# MSI001_MSI2500.net
KiCad netlist of a schematic drawn in Altium Designer
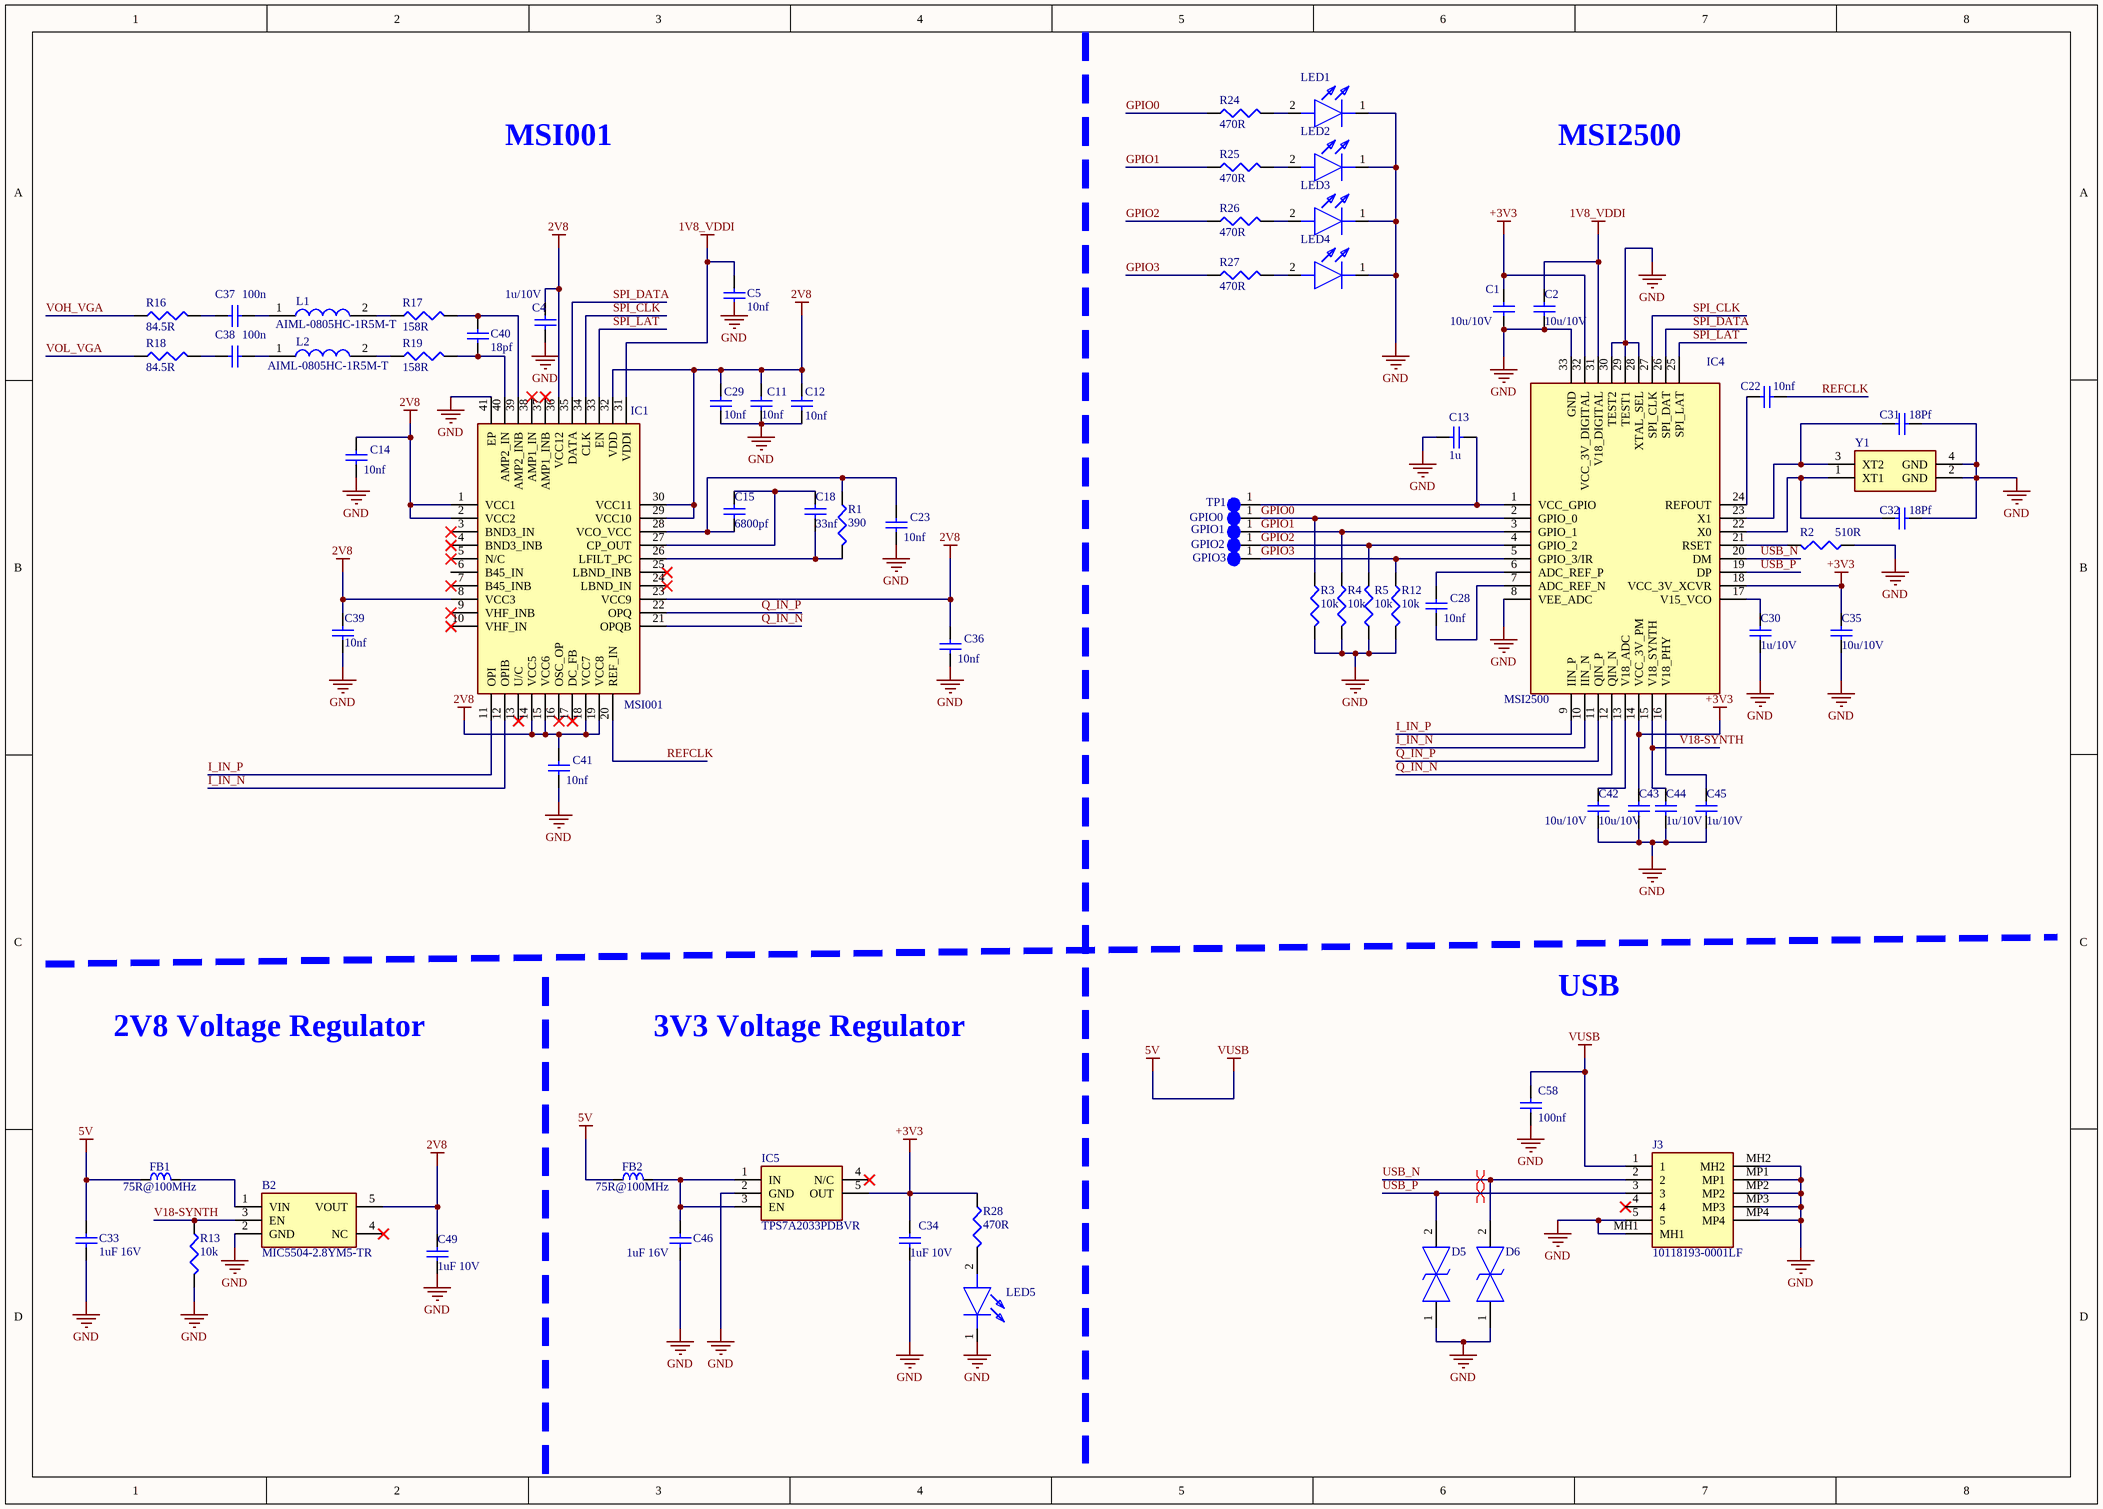
[diagram p0: MSI001 & MSI2500 .SchDoc]

(export (version "E")
  (design (tool "Eeschema 10.0.6"))
  (components
    (comp (ref "B2")
      (value "MIC5504-2.8YM5-TR")
      (footprint "SOT95P280X145-5N")
      (description "MICROCHIP - MIC5504-2.8YM5-TR - LDO VOLT REG, 0.3A, 2.8V, SOT-23-5")
      (fields (field (name "MOUSER PART NUMBER") "998-MIC5504-2.8YM5TR"))
      (libsource (lib "MIC5504-2.8YM5-TR") (part "MIC5504-2.8YM5-TR"))
    )
    (comp (ref "C1")
      (value "10u/10V")
      (footprint "0402_C")
      (description "Capacitor  0603 inch")
      (fields (field (name "Comment") "cap0603") (field (name "PUBLISHER") "Altium Limited"))
      (libsource (lib "alt2017") (part "cap0603"))
    )
    (comp (ref "C2")
      (value "10u/10V")
      (footprint "0402_C")
      (description "Capacitor  0603 inch")
      (fields (field (name "Comment") "cap0603") (field (name "PUBLISHER") "Altium Limited"))
      (libsource (lib "alt2017") (part "cap0603"))
    )
    (comp (ref "C4")
      (value "1u/10V")
      (footprint "0402_C")
      (description "Capacitor  0603 inch")
      (fields (field (name "Comment") "cap0603") (field (name "PUBLISHER") "Altium Limited"))
      (libsource (lib "alt2017") (part "cap0603"))
    )
    (comp (ref "C5")
      (value "10nf")
      (footprint "0402_C")
      (description "Capacitor  0402 inch")
      (fields (field (name "Comment") "cap0402") (field (name "PUBLISHER") "Altium Limited"))
      (libsource (lib "alt2017") (part "cap0603"))
    )
    (comp (ref "C11")
      (value "10nf")
      (footprint "0402_C")
      (description "Capacitor  0402 inch")
      (fields (field (name "Comment") "cap0402") (field (name "PUBLISHER") "Altium Limited"))
      (libsource (lib "alt2017") (part "cap0603"))
    )
    (comp (ref "C12")
      (value "10nf")
      (footprint "0402_C")
      (description "Capacitor  0402 inch")
      (fields (field (name "Comment") "cap0402") (field (name "PUBLISHER") "Altium Limited"))
      (libsource (lib "alt2017") (part "cap0603"))
    )
    (comp (ref "C13")
      (value "1u")
      (footprint "0402_C")
      (description "Capacitor  0603 inch")
      (fields (field (name "Comment") "cap0603") (field (name "PUBLISHER") "Altium Limited"))
      (libsource (lib "alt2017") (part "cap0603"))
    )
    (comp (ref "C14")
      (value "10nf")
      (footprint "0402_C")
      (description "Capacitor  0402 inch")
      (fields (field (name "Comment") "cap0402") (field (name "PUBLISHER") "Altium Limited"))
      (libsource (lib "alt2017") (part "cap0603"))
    )
    (comp (ref "C15")
      (value "6800pf")
      (footprint "0402_C")
      (description "Capacitor  0402 inch")
      (fields (field (name "Comment") "cap0402") (field (name "PUBLISHER") "Altium Limited"))
      (libsource (lib "alt2017") (part "cap0603"))
    )
    (comp (ref "C18")
      (value "33nf")
      (footprint "0402_C")
      (description "Capacitor  0402 inch")
      (fields (field (name "Comment") "cap0402") (field (name "PUBLISHER") "Altium Limited"))
      (libsource (lib "alt2017") (part "cap0603"))
    )
    (comp (ref "C22")
      (value "10nf")
      (footprint "0402_C")
      (description "Capacitor  0402 inch")
      (fields (field (name "Comment") "cap0402") (field (name "PUBLISHER") "Altium Limited"))
      (libsource (lib "alt2017") (part "cap0603"))
    )
    (comp (ref "C23")
      (value "10nf")
      (footprint "0402_C")
      (description "Capacitor  0402 inch")
      (fields (field (name "Comment") "cap0402") (field (name "PUBLISHER") "Altium Limited"))
      (libsource (lib "alt2017") (part "cap0603"))
    )
    (comp (ref "C28")
      (value "10nf")
      (footprint "0402_C")
      (description "Capacitor  0402 inch")
      (fields (field (name "Comment") "cap0402") (field (name "PUBLISHER") "Altium Limited"))
      (libsource (lib "alt2017") (part "cap0603"))
    )
    (comp (ref "C29")
      (value "10nf")
      (footprint "0402_C")
      (description "Capacitor  0402 inch")
      (fields (field (name "Comment") "cap0402") (field (name "PUBLISHER") "Altium Limited"))
      (libsource (lib "alt2017") (part "cap0603"))
    )
    (comp (ref "C30")
      (value "1u/10V")
      (footprint "0402_C")
      (description "Capacitor  0603 inch")
      (fields (field (name "Comment") "cap0603") (field (name "PUBLISHER") "Altium Limited"))
      (libsource (lib "alt2017") (part "cap0603"))
    )
    (comp (ref "C31")
      (value "18Pf")
      (footprint "0402_C")
      (description "Capacitor  0402 inch")
      (fields (field (name "Comment") "cap0402") (field (name "PUBLISHER") "Altium Limited"))
      (libsource (lib "alt2017") (part "cap0603"))
    )
    (comp (ref "C32")
      (value "18Pf")
      (footprint "0402_C")
      (description "Capacitor  0402 inch")
      (fields (field (name "Comment") "cap0402") (field (name "PUBLISHER") "Altium Limited"))
      (libsource (lib "alt2017") (part "cap0603"))
    )
    (comp (ref "C33")
      (value "1uF 16V")
      (footprint "SM0603 _3D_cap")
      (description "Capacitor  0603 inch")
      (fields (field (name "Comment") "cap0603") (field (name "PUBLISHER") "Altium Limited"))
      (libsource (lib "alt2017") (part "cap0603"))
    )
    (comp (ref "C34")
      (value "1uF 10V")
      (footprint "0402_C")
      (description "Capacitor  0603 inch")
      (fields (field (name "Comment") "cap0603") (field (name "PUBLISHER") "Altium Limited"))
      (libsource (lib "alt2017") (part "cap0603"))
    )
    (comp (ref "C35")
      (value "10u/10V")
      (footprint "0402_C")
      (description "Capacitor  0603 inch")
      (fields (field (name "Comment") "cap0603") (field (name "PUBLISHER") "Altium Limited"))
      (libsource (lib "alt2017") (part "cap0603"))
    )
    (comp (ref "C36")
      (value "10nf")
      (footprint "0402_C")
      (description "Capacitor  0402 inch")
      (fields (field (name "Comment") "cap0402") (field (name "PUBLISHER") "Altium Limited"))
      (libsource (lib "alt2017") (part "cap0603"))
    )
    (comp (ref "C37")
      (value "100n")
      (footprint "0402_C")
      (description "Capacitor  0402 inch")
      (fields (field (name "Comment") "cap0402") (field (name "PUBLISHER") "Altium Limited"))
      (libsource (lib "alt2017") (part "cap0603"))
    )
    (comp (ref "C38")
      (value "100n")
      (footprint "0402_C")
      (description "Capacitor  0402 inch")
      (fields (field (name "Comment") "cap0402") (field (name "PUBLISHER") "Altium Limited"))
      (libsource (lib "alt2017") (part "cap0603"))
    )
    (comp (ref "C39")
      (value "10nf")
      (footprint "0402_C")
      (description "Capacitor  0402 inch")
      (fields (field (name "Comment") "cap0402") (field (name "PUBLISHER") "Altium Limited"))
      (libsource (lib "alt2017") (part "cap0603"))
    )
    (comp (ref "C40")
      (value "18pf")
      (footprint "0402_C")
      (description "Capacitor  0402 inch")
      (fields (field (name "Comment") "cap0402") (field (name "PUBLISHER") "Altium Limited"))
      (libsource (lib "alt2017") (part "cap0603"))
    )
    (comp (ref "C41")
      (value "10nf")
      (footprint "0402_C")
      (description "Capacitor  0402 inch")
      (fields (field (name "Comment") "cap0402") (field (name "PUBLISHER") "Altium Limited"))
      (libsource (lib "alt2017") (part "cap0603"))
    )
    (comp (ref "C42")
      (value "10u/10V")
      (footprint "0402_C")
      (description "Capacitor  0603 inch")
      (fields (field (name "Comment") "cap0603") (field (name "PUBLISHER") "Altium Limited"))
      (libsource (lib "alt2017") (part "cap0603"))
    )
    (comp (ref "C43")
      (value "10u/10V")
      (footprint "0402_C")
      (description "Capacitor  0603 inch")
      (fields (field (name "Comment") "cap0603") (field (name "PUBLISHER") "Altium Limited"))
      (libsource (lib "alt2017") (part "cap0603"))
    )
    (comp (ref "C44")
      (value "1u/10V")
      (footprint "0402_C")
      (description "Capacitor  0603 inch")
      (fields (field (name "Comment") "cap0603") (field (name "PUBLISHER") "Altium Limited"))
      (libsource (lib "alt2017") (part "cap0603"))
    )
    (comp (ref "C45")
      (value "1u/10V")
      (footprint "0402_C")
      (description "Capacitor  0603 inch")
      (fields (field (name "Comment") "cap0603") (field (name "PUBLISHER") "Altium Limited"))
      (libsource (lib "alt2017") (part "cap0603"))
    )
    (comp (ref "C46")
      (value "1uF 16V")
      (footprint "SM0603 _3D_cap")
      (description "Capacitor  0603 inch")
      (fields (field (name "Comment") "cap0603") (field (name "PUBLISHER") "Altium Limited"))
      (libsource (lib "alt2017") (part "cap0603"))
    )
    (comp (ref "C49")
      (value "1uF 10V")
      (footprint "0402_C")
      (description "Capacitor  0603 inch")
      (fields (field (name "Comment") "cap0603") (field (name "PUBLISHER") "Altium Limited"))
      (libsource (lib "alt2017") (part "cap0603"))
    )
    (comp (ref "C58")
      (value "100nf")
      (footprint "0402_C")
      (description "Capacitor  0402 inch")
      (fields (field (name "Comment") "cap0402") (field (name "PUBLISHER") "Altium Limited"))
      (libsource (lib "alt2017") (part "cap0603"))
    )
    (comp (ref "D5")
      (value "ESD101B102ELSE6327XTSA1")
      (footprint "shunt_resistor:ESD207B102ELE6327")
      (description "TVS Diode (Bi-directional)")
      (fields (field (name "MOUSER PART NUMBER") "726-ESD101B102ELSE63"))
      (libsource (lib "*") (part "ESD101B102ELSE6327XTSA1"))
    )
    (comp (ref "D6")
      (value "ESD101B102ELSE6327XTSA1")
      (footprint "shunt_resistor:ESD207B102ELE6327")
      (description "TVS Diode (Bi-directional)")
      (fields (field (name "MOUSER PART NUMBER") "726-ESD101B102ELSE63"))
      (libsource (lib "*") (part "ESD101B102ELSE6327XTSA1"))
    )
    (comp (ref "FB1")
      (value "75R@100MHz")
      (footprint "SM0603_3D_res")
      (description "chip inductance 0603")
      (fields
        (field (name "PART NUMBER") "IND0805_MURATA_BLM21BB750SN1D")
        (field (name "POWER") "700mA")
        (field (name "AUTHOR") "S. Jafar")
      )
      (libsource (lib "alt_vovan") (part "chip inductance 0603"))
    )
    (comp (ref "FB2")
      (value "75R@100MHz")
      (footprint "SM0603_3D_res")
      (description "chip inductance 0603")
      (fields
        (field (name "PART NUMBER") "IND0805_MURATA_BLM21BB750SN1D")
        (field (name "POWER") "700mA")
        (field (name "AUTHOR") "S. Jafar")
      )
      (libsource (lib "alt_vovan") (part "chip inductance 0603"))
    )
    (comp (ref "GPIO0")
      (value "TP")
      (footprint "TP_1mm")
      (description "Connector")
      (fields (field (name "MANUFACTURER_PART_NUMBER") "050/LT/B2"))
      (libsource (lib "Lib") (part "Test Point"))
    )
    (comp (ref "GPIO1")
      (value "TP")
      (footprint "TP_1mm")
      (description "Connector")
      (fields (field (name "MANUFACTURER_PART_NUMBER") "050/LT/B2"))
      (libsource (lib "Lib") (part "Test Point"))
    )
    (comp (ref "GPIO2")
      (value "TP")
      (footprint "TP_1mm")
      (description "Connector")
      (fields (field (name "MANUFACTURER_PART_NUMBER") "050/LT/B2"))
      (libsource (lib "Lib") (part "Test Point"))
    )
    (comp (ref "GPIO3")
      (value "TP")
      (footprint "TP_1mm")
      (description "Connector")
      (fields (field (name "MANUFACTURER_PART_NUMBER") "050/LT/B2"))
      (libsource (lib "Lib") (part "Test Point"))
    )
    (comp (ref "IC1")
      (value "MSI001")
      (footprint "shunt_resistor:QFN50P600X600X90-41N-D")
      (description "Integrated Circuit")
      (libsource (lib "*") (part "MSI001"))
    )
    (comp (ref "IC4")
      (value "MSI2500")
      (footprint "shunt_resistor:QFN50P500X500X90-33N-D")
      (description "Connector")
      (libsource (lib "*") (part "MSI2500"))
    )
    (comp (ref "IC5")
      (value "TPS7A2033PDBVR")
      (footprint "shunt_resistor:SOT95P280X145-5N")
      (description "Integrated Circuit")
      (fields
        (field (name "MANUFACTURER_PART_NUMBER") "TPS7A2050PDBVR")
        (field (name "MOUSER PART NUMBER") "595-TPS7A2050PDBVR")
      )
      (libsource (lib "*") (part "TPS7A2050PDBVR"))
    )
    (comp (ref "J3")
      (value "10118193-0001LF")
      (footprint "shunt_resistor:101181930001LF")
      (description "Connector")
      (fields (field (name "MOUSER PART NUMBER") "649-10118193-0001LF"))
      (libsource (lib "*") (part "10118193-0001LF"))
    )
    (comp (ref "L1")
      (value "AIML-0805HC-1R5M-T")
      (footprint "shunt_resistor:INDC2012X95N")
      (description "Inductor")
      (fields (field (name "MOUSER PART NUMBER") "815-AIML-0805HC1R5MT"))
      (libsource (lib "shunt_resistor") (part "AIML-0805HC-1R5M-T"))
    )
    (comp (ref "L2")
      (value "AIML-0805HC-1R5M-T")
      (footprint "shunt_resistor:INDC2012X95N")
      (description "Inductor")
      (fields (field (name "MOUSER PART NUMBER") "815-AIML-0805HC1R5MT"))
      (libsource (lib "shunt_resistor") (part "AIML-0805HC-1R5M-T"))
    )
    (comp (ref "LED1")
      (value "LTST-C190GKT")
      (footprint "shunt_resistor:LEDC1608X90N")
      (description "LED")
      (fields (field (name "MOUSER PART NUMBER") "859-LTST-C190GKT"))
      (libsource (lib "shunt_resistor") (part "LTST-C190GKT"))
    )
    (comp (ref "LED2")
      (value "LTST-C190GKT")
      (footprint "shunt_resistor:LEDC1608X90N")
      (description "LED")
      (fields (field (name "MOUSER PART NUMBER") "859-LTST-C190GKT"))
      (libsource (lib "shunt_resistor") (part "LTST-C190GKT"))
    )
    (comp (ref "LED3")
      (value "LTST-C190GKT")
      (footprint "shunt_resistor:LEDC1608X90N")
      (description "LED")
      (fields (field (name "MOUSER PART NUMBER") "859-LTST-C190GKT"))
      (libsource (lib "shunt_resistor") (part "LTST-C190GKT"))
    )
    (comp (ref "LED4")
      (value "LTST-C190GKT")
      (footprint "shunt_resistor:LEDC1608X90N")
      (description "LED")
      (fields (field (name "MOUSER PART NUMBER") "859-LTST-C190GKT"))
      (libsource (lib "shunt_resistor") (part "LTST-C190GKT"))
    )
    (comp (ref "LED5")
      (value "LTST-C190GKT")
      (footprint "shunt_resistor:LEDC1608X90N")
      (description "LED")
      (fields (field (name "MOUSER PART NUMBER") "859-LTST-C190GKT"))
      (libsource (lib "shunt_resistor") (part "LTST-C190GKT"))
    )
    (comp (ref "R1")
      (value "390")
      (footprint "0402_R")
      (description "RES 280 OHM 1/16W 0402 SMD")
      (libsource (lib "Integrated_Library_RF_FEB_2012") (part "RC0402FR-0710KL"))
    )
    (comp (ref "R2")
      (value "510R")
      (footprint "0402_R")
      (description "RES 280 OHM 1/16W 0402 SMD")
      (libsource (lib "Integrated_Library_RF_FEB_2012") (part "RC0402FR-0710KL"))
    )
    (comp (ref "R3")
      (value "10k")
      (footprint "0402_R")
      (description "RES 10K OHM 1/16W 1% 0402 SMD")
      (libsource (lib "Integrated_Library_RF_FEB_2012") (part "RC0402FR-0710KL"))
    )
    (comp (ref "R4")
      (value "10k")
      (footprint "0402_R")
      (description "RES 10K OHM 1/16W 1% 0402 SMD")
      (libsource (lib "Integrated_Library_RF_FEB_2012") (part "RC0402FR-0710KL"))
    )
    (comp (ref "R5")
      (value "10k")
      (footprint "0402_R")
      (description "RES 10K OHM 1/16W 1% 0402 SMD")
      (libsource (lib "Integrated_Library_RF_FEB_2012") (part "RC0402FR-0710KL"))
    )
    (comp (ref "R12")
      (value "10k")
      (footprint "0402_R")
      (description "RES 10K OHM 1/16W 1% 0402 SMD")
      (libsource (lib "Integrated_Library_RF_FEB_2012") (part "RC0402FR-0710KL"))
    )
    (comp (ref "R13")
      (value "10k")
      (footprint "0402_R")
      (description "RES 10K OHM 1/16W 1% 0402 SMD")
      (libsource (lib "Integrated_Library_RF_FEB_2012") (part "RC0402FR-0710KL"))
    )
    (comp (ref "R16")
      (value "84.5R")
      (footprint "0402_R")
      (description "RES 10K OHM 1/16W 0402 SMD")
      (libsource (lib "Integrated_Library_RF_FEB_2012") (part "RC0402FR-0710KL"))
    )
    (comp (ref "R17")
      (value "158R")
      (footprint "0402_R")
      (description "RES 18 OHM 1/16W 0402 SMD")
      (libsource (lib "Integrated_Library_RF_FEB_2012") (part "RC0402FR-0710KL"))
    )
    (comp (ref "R18")
      (value "84.5R")
      (footprint "0402_R")
      (description "RES 10K OHM 1/16W 0402 SMD")
      (libsource (lib "Integrated_Library_RF_FEB_2012") (part "RC0402FR-0710KL"))
    )
    (comp (ref "R19")
      (value "158R")
      (footprint "0402_R")
      (description "RES 18 OHM 1/16W 0402 SMD")
      (libsource (lib "Integrated_Library_RF_FEB_2012") (part "RC0402FR-0710KL"))
    )
    (comp (ref "R24")
      (value "470R")
      (footprint "0402_R")
      (description "RES 10K OHM 1/16W 1% 0402 SMD")
      (libsource (lib "Integrated_Library_RF_FEB_2012") (part "RC0402FR-0710KL"))
    )
    (comp (ref "R25")
      (value "470R")
      (footprint "0402_R")
      (description "RES 10K OHM 1/16W 1% 0402 SMD")
      (libsource (lib "Integrated_Library_RF_FEB_2012") (part "RC0402FR-0710KL"))
    )
    (comp (ref "R26")
      (value "470R")
      (footprint "0402_R")
      (description "RES 10K OHM 1/16W 1% 0402 SMD")
      (libsource (lib "Integrated_Library_RF_FEB_2012") (part "RC0402FR-0710KL"))
    )
    (comp (ref "R27")
      (value "470R")
      (footprint "0402_R")
      (description "RES 10K OHM 1/16W 1% 0402 SMD")
      (libsource (lib "Integrated_Library_RF_FEB_2012") (part "RC0402FR-0710KL"))
    )
    (comp (ref "R28")
      (value "470R")
      (footprint "0402_R")
      (description "RES 10K OHM 1/16W 1% 0402 SMD")
      (libsource (lib "Integrated_Library_RF_FEB_2012") (part "RC0402FR-0710KL"))
    )
    (comp (ref "TP1")
      (value "TP")
      (footprint "TP_1mm")
      (description "Connector")
      (fields (field (name "MANUFACTURER_PART_NUMBER") "050/LT/B2"))
      (libsource (lib "Lib") (part "Test Point"))
    )
    (comp (ref "Y1")
      (value "ABM8G-24.000MHZ-18-D2Y-T")
      (footprint "shunt_resistor:ABM8G")
      (description "Crystal or Oscillator")
      (fields (field (name "MOUSER PART NUMBER") "815-ABM8G-24-18-D2Y"))
      (libsource (lib "shunt_resistor") (part "ABM8G-24.000MHZ-18-D2Y-T"))
    )
  )
  (nets
    (net (code "1") (name "+3V3") (class "Default")
      (node (ref "C1") (pin "2") (pinfunction "2_2") (pintype "passive"))
      (node (ref "C34") (pin "1") (pinfunction "1_1") (pintype "passive"))
      (node (ref "C35") (pin "1") (pinfunction "1_1") (pintype "passive"))
      (node (ref "C43") (pin "1") (pinfunction "1_1") (pintype "passive"))
      (node (ref "IC4") (pin "14") (pinfunction "VCC_3V_PM_14") (pintype "passive"))
      (node (ref "IC4") (pin "18") (pinfunction "VCC_3V_XCVR_18") (pintype "passive"))
      (node (ref "IC4") (pin "32") (pinfunction "VCC_3V_DIGITAL_32") (pintype "passive"))
      (node (ref "IC5") (pin "5") (pinfunction "OUT_5") (pintype "passive"))
      (node (ref "R28") (pin "1") (pinfunction "1_1") (pintype "passive"))
    )
    (net (code "2") (name "/GPIO0") (class "Default")
      (node (ref "GPIO0") (pin "1") (pinfunction "1_1") (pintype "passive"))
      (node (ref "IC4") (pin "2") (pinfunction "GPIO_0_2") (pintype "passive"))
      (node (ref "R24") (pin "1") (pinfunction "1_1") (pintype "passive"))
      (node (ref "R3") (pin "1") (pinfunction "1_1") (pintype "passive"))
    )
    (net (code "3") (name "/GPIO1") (class "Default")
      (node (ref "GPIO1") (pin "1") (pinfunction "1_1") (pintype "passive"))
      (node (ref "IC4") (pin "3") (pinfunction "GPIO_1_3") (pintype "passive"))
      (node (ref "R25") (pin "1") (pinfunction "1_1") (pintype "passive"))
      (node (ref "R4") (pin "1") (pinfunction "1_1") (pintype "passive"))
    )
    (net (code "4") (name "/GPIO2") (class "Default")
      (node (ref "GPIO2") (pin "1") (pinfunction "1_1") (pintype "passive"))
      (node (ref "IC4") (pin "4") (pinfunction "GPIO_2_4") (pintype "passive"))
      (node (ref "R26") (pin "1") (pinfunction "1_1") (pintype "passive"))
      (node (ref "R5") (pin "2") (pinfunction "2_2") (pintype "passive"))
    )
    (net (code "5") (name "/GPIO3") (class "Default")
      (node (ref "GPIO3") (pin "1") (pinfunction "1_1") (pintype "passive"))
      (node (ref "IC4") (pin "5") (pinfunction "GPIO_3/IR_5") (pintype "passive"))
      (node (ref "R12") (pin "1") (pinfunction "1_1") (pintype "passive"))
      (node (ref "R27") (pin "1") (pinfunction "1_1") (pintype "passive"))
    )
    (net (code "6") (name "/I_IN_N") (class "Default")
      (node (ref "IC1") (pin "12") (pinfunction "OPIB_12") (pintype "passive"))
      (node (ref "IC4") (pin "10") (pinfunction "IIN_N_10") (pintype "passive"))
    )
    (net (code "7") (name "/I_IN_P") (class "Default")
      (node (ref "IC1") (pin "11") (pinfunction "OPI_11") (pintype "passive"))
      (node (ref "IC4") (pin "9") (pinfunction "IIN_P_9") (pintype "passive"))
    )
    (net (code "8") (name "/Q_IN_N") (class "Default")
      (node (ref "IC1") (pin "21") (pinfunction "OPQB_21") (pintype "passive"))
      (node (ref "IC4") (pin "12") (pinfunction "QIN_N_12") (pintype "passive"))
    )
    (net (code "9") (name "/Q_IN_P") (class "Default")
      (node (ref "IC1") (pin "22") (pinfunction "OPQ_22") (pintype "passive"))
      (node (ref "IC4") (pin "11") (pinfunction "QIN_P_11") (pintype "passive"))
    )
    (net (code "10") (name "/REFCLK") (class "Default")
      (node (ref "C22") (pin "1") (pinfunction "1_1") (pintype "passive"))
      (node (ref "IC1") (pin "20") (pinfunction "REF_IN_20") (pintype "passive"))
    )
    (net (code "11") (name "/SPI_CLK") (class "Default")
      (node (ref "IC1") (pin "34") (pinfunction "CLK_34") (pintype "passive"))
      (node (ref "IC4") (pin "27") (pinfunction "SPI_CLK_27") (pintype "passive"))
    )
    (net (code "12") (name "/SPI_DATA") (class "Default")
      (node (ref "IC1") (pin "35") (pinfunction "DATA_35") (pintype "passive"))
      (node (ref "IC4") (pin "26") (pinfunction "SPI_DAT_26") (pintype "passive"))
    )
    (net (code "13") (name "/SPI_LAT") (class "Default")
      (node (ref "IC1") (pin "33") (pinfunction "EN_33") (pintype "passive"))
      (node (ref "IC4") (pin "25") (pinfunction "SPI_LAT_25") (pintype "passive"))
    )
    (net (code "14") (name "/USB_N") (class "Default")
      (node (ref "D6") (pin "2") (pinfunction "2_2") (pintype "passive"))
      (node (ref "IC4") (pin "20") (pinfunction "DM_20") (pintype "passive"))
      (node (ref "J3") (pin "2") (pinfunction "2_2") (pintype "passive"))
    )
    (net (code "15") (name "/USB_P") (class "Default")
      (node (ref "D5") (pin "2") (pinfunction "2_2") (pintype "passive"))
      (node (ref "IC4") (pin "19") (pinfunction "DP_19") (pintype "passive"))
      (node (ref "J3") (pin "3") (pinfunction "3_3") (pintype "passive"))
    )
    (net (code "16") (name "/V18-SYNTH") (class "Default")
      (node (ref "B2") (pin "3") (pinfunction "EN_3") (pintype "passive"))
      (node (ref "C44") (pin "1") (pinfunction "1_1") (pintype "passive"))
      (node (ref "IC4") (pin "15") (pinfunction "V18_SYNTH_15") (pintype "passive"))
      (node (ref "R13") (pin "1") (pinfunction "1_1") (pintype "passive"))
    )
    (net (code "17") (name "/VOH_VGA") (class "Default")
      (node (ref "R16") (pin "1") (pinfunction "1_1") (pintype "passive"))
    )
    (net (code "18") (name "/VOL_VGA") (class "Default")
      (node (ref "R18") (pin "1") (pinfunction "1_1") (pintype "passive"))
    )
    (net (code "19") (name "1V8_VDDI") (class "Default")
      (node (ref "C2") (pin "2") (pinfunction "2_2") (pintype "passive"))
      (node (ref "C5") (pin "1") (pinfunction "1_1") (pintype "passive"))
      (node (ref "IC1") (pin "31") (pinfunction "VDDI_31") (pintype "passive"))
      (node (ref "IC4") (pin "31") (pinfunction "V18_DIGITAL_31") (pintype "passive"))
    )
    (net (code "20") (name "2V8") (class "Default")
      (node (ref "B2") (pin "5") (pinfunction "VOUT_5") (pintype "passive"))
      (node (ref "C11") (pin "1") (pinfunction "1_1") (pintype "passive"))
      (node (ref "C12") (pin "1") (pinfunction "1_1") (pintype "passive"))
      (node (ref "C14") (pin "2") (pinfunction "2_2") (pintype "passive"))
      (node (ref "C29") (pin "1") (pinfunction "1_1") (pintype "passive"))
      (node (ref "C36") (pin "2") (pinfunction "2_2") (pintype "passive"))
      (node (ref "C39") (pin "2") (pinfunction "2_2") (pintype "passive"))
      (node (ref "C4") (pin "1") (pinfunction "1_1") (pintype "passive"))
      (node (ref "C41") (pin "2") (pinfunction "2_2") (pintype "passive"))
      (node (ref "C49") (pin "1") (pinfunction "1_1") (pintype "passive"))
      (node (ref "IC1") (pin "1") (pinfunction "VCC1_1") (pintype "passive"))
      (node (ref "IC1") (pin "14") (pinfunction "VCC5_14") (pintype "passive"))
      (node (ref "IC1") (pin "15") (pinfunction "VCC6_15") (pintype "passive"))
      (node (ref "IC1") (pin "18") (pinfunction "VCC7_18") (pintype "passive"))
      (node (ref "IC1") (pin "19") (pinfunction "VCC8_19") (pintype "passive"))
      (node (ref "IC1") (pin "2") (pinfunction "VCC2_2") (pintype "passive"))
      (node (ref "IC1") (pin "23") (pinfunction "VCC9_23") (pintype "passive"))
      (node (ref "IC1") (pin "29") (pinfunction "VCC10_29") (pintype "passive"))
      (node (ref "IC1") (pin "30") (pinfunction "VCC11_30") (pintype "passive"))
      (node (ref "IC1") (pin "32") (pinfunction "VDD_32") (pintype "passive"))
      (node (ref "IC1") (pin "36") (pinfunction "VCC12_36") (pintype "passive"))
      (node (ref "IC1") (pin "8") (pinfunction "VCC3_8") (pintype "passive"))
    )
    (net (code "21") (name "5V") (class "Default")
      (node (ref "C33") (pin "2") (pinfunction "2_2") (pintype "passive"))
      (node (ref "C58") (pin "2") (pinfunction "2_2") (pintype "passive"))
      (node (ref "FB1") (pin "1") (pinfunction "1_1") (pintype "passive"))
      (node (ref "FB2") (pin "1") (pinfunction "1_1") (pintype "passive"))
      (node (ref "J3") (pin "1") (pinfunction "1_1") (pintype "passive"))
    )
    (net (code "22") (name "GND") (class "Default")
      (node (ref "B2") (pin "2") (pinfunction "GND_2") (pintype "passive"))
      (node (ref "C1") (pin "1") (pinfunction "1_1") (pintype "passive"))
      (node (ref "C11") (pin "2") (pinfunction "2_2") (pintype "passive"))
      (node (ref "C12") (pin "2") (pinfunction "2_2") (pintype "passive"))
      (node (ref "C13") (pin "1") (pinfunction "1_1") (pintype "passive"))
      (node (ref "C14") (pin "1") (pinfunction "1_1") (pintype "passive"))
      (node (ref "C2") (pin "1") (pinfunction "1_1") (pintype "passive"))
      (node (ref "C23") (pin "1") (pinfunction "1_1") (pintype "passive"))
      (node (ref "C29") (pin "2") (pinfunction "2_2") (pintype "passive"))
      (node (ref "C30") (pin "2") (pinfunction "2_2") (pintype "passive"))
      (node (ref "C31") (pin "1") (pinfunction "1_1") (pintype "passive"))
      (node (ref "C32") (pin "1") (pinfunction "1_1") (pintype "passive"))
      (node (ref "C33") (pin "1") (pinfunction "1_1") (pintype "passive"))
      (node (ref "C34") (pin "2") (pinfunction "2_2") (pintype "passive"))
      (node (ref "C35") (pin "2") (pinfunction "2_2") (pintype "passive"))
      (node (ref "C36") (pin "1") (pinfunction "1_1") (pintype "passive"))
      (node (ref "C39") (pin "1") (pinfunction "1_1") (pintype "passive"))
      (node (ref "C4") (pin "2") (pinfunction "2_2") (pintype "passive"))
      (node (ref "C41") (pin "1") (pinfunction "1_1") (pintype "passive"))
      (node (ref "C42") (pin "2") (pinfunction "2_2") (pintype "passive"))
      (node (ref "C43") (pin "2") (pinfunction "2_2") (pintype "passive"))
      (node (ref "C44") (pin "2") (pinfunction "2_2") (pintype "passive"))
      (node (ref "C45") (pin "2") (pinfunction "2_2") (pintype "passive"))
      (node (ref "C46") (pin "1") (pinfunction "1_1") (pintype "passive"))
      (node (ref "C49") (pin "2") (pinfunction "2_2") (pintype "passive"))
      (node (ref "C58") (pin "1") (pinfunction "1_1") (pintype "passive"))
      (node (ref "D5") (pin "1") (pinfunction "1_1") (pintype "passive"))
      (node (ref "D6") (pin "1") (pinfunction "1_1") (pintype "passive"))
      (node (ref "IC1") (pin "41") (pinfunction "EP_41") (pintype "passive"))
      (node (ref "IC4") (pin "28") (pinfunction "XTAL_SEL_28") (pintype "passive"))
      (node (ref "IC4") (pin "29") (pinfunction "TEST1_29") (pintype "passive"))
      (node (ref "IC4") (pin "30") (pinfunction "TEST2_30") (pintype "passive"))
      (node (ref "IC4") (pin "33") (pinfunction "GND_33") (pintype "passive"))
      (node (ref "IC4") (pin "8") (pinfunction "VEE_ADC_8") (pintype "passive"))
      (node (ref "IC5") (pin "2") (pinfunction "GND_2") (pintype "passive"))
      (node (ref "J3") (pin "5") (pinfunction "5_5") (pintype "passive"))
      (node (ref "J3") (pin "MH1") (pinfunction "MH1_MH1") (pintype "passive"))
      (node (ref "J3") (pin "MH2") (pinfunction "MH2_MH2") (pintype "passive"))
      (node (ref "J3") (pin "MP1") (pinfunction "MP1_MP1") (pintype "passive"))
      (node (ref "J3") (pin "MP2") (pinfunction "MP2_MP2") (pintype "passive"))
      (node (ref "J3") (pin "MP3") (pinfunction "MP3_MP3") (pintype "passive"))
      (node (ref "J3") (pin "MP4") (pinfunction "MP4_MP4") (pintype "passive"))
      (node (ref "LED1") (pin "1") (pinfunction "K_1") (pintype "passive"))
      (node (ref "LED2") (pin "1") (pinfunction "K_1") (pintype "passive"))
      (node (ref "LED3") (pin "1") (pinfunction "K_1") (pintype "passive"))
      (node (ref "LED4") (pin "1") (pinfunction "K_1") (pintype "passive"))
      (node (ref "LED5") (pin "1") (pinfunction "K_1") (pintype "passive"))
      (node (ref "R12") (pin "2") (pinfunction "2_2") (pintype "passive"))
      (node (ref "R13") (pin "2") (pinfunction "2_2") (pintype "passive"))
      (node (ref "R2") (pin "1") (pinfunction "1_1") (pintype "passive"))
      (node (ref "R3") (pin "2") (pinfunction "2_2") (pintype "passive"))
      (node (ref "R4") (pin "2") (pinfunction "2_2") (pintype "passive"))
      (node (ref "R5") (pin "1") (pinfunction "1_1") (pintype "passive"))
      (node (ref "Y1") (pin "2") (pinfunction "GND_2") (pintype "passive"))
      (node (ref "Y1") (pin "4") (pinfunction "GND_4") (pintype "passive"))
    )
    (net (code "23") (name "Net-(B2-VIN)") (class "Default")
      (node (ref "B2") (pin "1") (pinfunction "VIN_1") (pintype "passive"))
      (node (ref "FB1") (pin "2") (pinfunction "2_2") (pintype "passive"))
    )
    (net (code "24") (name "Net-(C37-Pad1)") (class "Default")
      (node (ref "C37") (pin "1") (pinfunction "1_1") (pintype "passive"))
      (node (ref "L1") (pin "1") (pinfunction "1_1") (pintype "passive"))
    )
    (net (code "25") (name "Net-(C37-Pad2)") (class "Default")
      (node (ref "C37") (pin "2") (pinfunction "2_2") (pintype "passive"))
      (node (ref "R16") (pin "2") (pinfunction "2_2") (pintype "passive"))
    )
    (net (code "26") (name "Net-(C38-Pad1)") (class "Default")
      (node (ref "C38") (pin "1") (pinfunction "1_1") (pintype "passive"))
      (node (ref "L2") (pin "1") (pinfunction "1_1") (pintype "passive"))
    )
    (net (code "27") (name "Net-(C38-Pad2)") (class "Default")
      (node (ref "C38") (pin "2") (pinfunction "2_2") (pintype "passive"))
      (node (ref "R18") (pin "2") (pinfunction "2_2") (pintype "passive"))
    )
    (net (code "28") (name "Net-(IC1-AMP2_IN)") (class "Default")
      (node (ref "C40") (pin "2") (pinfunction "2_2") (pintype "passive"))
      (node (ref "IC1") (pin "40") (pinfunction "AMP2_IN_40") (pintype "passive"))
      (node (ref "R19") (pin "2") (pinfunction "2_2") (pintype "passive"))
    )
    (net (code "29") (name "Net-(IC1-AMP2_INB)") (class "Default")
      (node (ref "C40") (pin "1") (pinfunction "1_1") (pintype "passive"))
      (node (ref "IC1") (pin "39") (pinfunction "AMP2_INB_39") (pintype "passive"))
      (node (ref "R17") (pin "2") (pinfunction "2_2") (pintype "passive"))
    )
    (net (code "30") (name "Net-(IC1-CP_OUT)") (class "Default")
      (node (ref "C15") (pin "1") (pinfunction "1_1") (pintype "passive"))
      (node (ref "C18") (pin "2") (pinfunction "2_2") (pintype "passive"))
      (node (ref "IC1") (pin "27") (pinfunction "CP_OUT_27") (pintype "passive"))
    )
    (net (code "31") (name "Net-(IC1-LFILT_PC)") (class "Default")
      (node (ref "C18") (pin "1") (pinfunction "1_1") (pintype "passive"))
      (node (ref "IC1") (pin "26") (pinfunction "LFILT_PC_26") (pintype "passive"))
      (node (ref "R1") (pin "2") (pinfunction "2_2") (pintype "passive"))
    )
    (net (code "32") (name "Net-(IC1-VCO_VCC)") (class "Default")
      (node (ref "C15") (pin "2") (pinfunction "2_2") (pintype "passive"))
      (node (ref "C23") (pin "2") (pinfunction "2_2") (pintype "passive"))
      (node (ref "IC1") (pin "28") (pinfunction "VCO_VCC_28") (pintype "passive"))
      (node (ref "R1") (pin "1") (pinfunction "1_1") (pintype "passive"))
    )
    (net (code "33") (name "Net-(IC4-ADC_REF_N)") (class "Default")
      (node (ref "C28") (pin "1") (pinfunction "1_1") (pintype "passive"))
      (node (ref "IC4") (pin "7") (pinfunction "ADC_REF_N_7") (pintype "passive"))
    )
    (net (code "34") (name "Net-(IC4-ADC_REF_P)") (class "Default")
      (node (ref "C28") (pin "2") (pinfunction "2_2") (pintype "passive"))
      (node (ref "IC4") (pin "6") (pinfunction "ADC_REF_P_6") (pintype "passive"))
    )
    (net (code "35") (name "Net-(IC4-REFOUT)") (class "Default")
      (node (ref "C22") (pin "2") (pinfunction "2_2") (pintype "passive"))
      (node (ref "IC4") (pin "24") (pinfunction "REFOUT_24") (pintype "passive"))
    )
    (net (code "36") (name "Net-(IC4-RSET)") (class "Default")
      (node (ref "IC4") (pin "21") (pinfunction "RSET_21") (pintype "passive"))
      (node (ref "R2") (pin "2") (pinfunction "2_2") (pintype "passive"))
    )
    (net (code "37") (name "Net-(IC4-V15_VCO)") (class "Default")
      (node (ref "C30") (pin "1") (pinfunction "1_1") (pintype "passive"))
      (node (ref "IC4") (pin "17") (pinfunction "V15_VCO_17") (pintype "passive"))
    )
    (net (code "38") (name "Net-(IC4-V18_ADC)") (class "Default")
      (node (ref "C42") (pin "1") (pinfunction "1_1") (pintype "passive"))
      (node (ref "IC4") (pin "13") (pinfunction "V18_ADC_13") (pintype "passive"))
    )
    (net (code "39") (name "Net-(IC4-V18_PHY)") (class "Default")
      (node (ref "C45") (pin "1") (pinfunction "1_1") (pintype "passive"))
      (node (ref "IC4") (pin "16") (pinfunction "V18_PHY_16") (pintype "passive"))
    )
    (net (code "40") (name "Net-(IC4-VCC_GPIO)") (class "Default")
      (node (ref "C13") (pin "2") (pinfunction "2_2") (pintype "passive"))
      (node (ref "IC4") (pin "1") (pinfunction "VCC_GPIO_1") (pintype "passive"))
      (node (ref "TP1") (pin "1") (pinfunction "1_1") (pintype "passive"))
    )
    (net (code "41") (name "Net-(IC4-X0)") (class "Default")
      (node (ref "C32") (pin "2") (pinfunction "2_2") (pintype "passive"))
      (node (ref "IC4") (pin "22") (pinfunction "X0_22") (pintype "passive"))
      (node (ref "Y1") (pin "1") (pinfunction "XT1_1") (pintype "passive"))
    )
    (net (code "42") (name "Net-(IC4-X1)") (class "Default")
      (node (ref "C31") (pin "2") (pinfunction "2_2") (pintype "passive"))
      (node (ref "IC4") (pin "23") (pinfunction "X1_23") (pintype "passive"))
      (node (ref "Y1") (pin "3") (pinfunction "XT2_3") (pintype "passive"))
    )
    (net (code "43") (name "Net-(IC5-EN)") (class "Default")
      (node (ref "C46") (pin "2") (pinfunction "2_2") (pintype "passive"))
      (node (ref "FB2") (pin "2") (pinfunction "2_2") (pintype "passive"))
      (node (ref "IC5") (pin "1") (pinfunction "IN_1") (pintype "passive"))
      (node (ref "IC5") (pin "3") (pinfunction "EN_3") (pintype "passive"))
    )
    (net (code "44") (name "Net-(L1-Pad2)") (class "Default")
      (node (ref "L1") (pin "2") (pinfunction "2_2") (pintype "passive"))
      (node (ref "R17") (pin "1") (pinfunction "1_1") (pintype "passive"))
    )
    (net (code "45") (name "Net-(L2-Pad2)") (class "Default")
      (node (ref "L2") (pin "2") (pinfunction "2_2") (pintype "passive"))
      (node (ref "R19") (pin "1") (pinfunction "1_1") (pintype "passive"))
    )
    (net (code "46") (name "Net-(LED1-A)") (class "Default")
      (node (ref "LED1") (pin "2") (pinfunction "A_2") (pintype "passive"))
      (node (ref "R24") (pin "2") (pinfunction "2_2") (pintype "passive"))
    )
    (net (code "47") (name "Net-(LED2-A)") (class "Default")
      (node (ref "LED2") (pin "2") (pinfunction "A_2") (pintype "passive"))
      (node (ref "R25") (pin "2") (pinfunction "2_2") (pintype "passive"))
    )
    (net (code "48") (name "Net-(LED3-A)") (class "Default")
      (node (ref "LED3") (pin "2") (pinfunction "A_2") (pintype "passive"))
      (node (ref "R26") (pin "2") (pinfunction "2_2") (pintype "passive"))
    )
    (net (code "49") (name "Net-(LED4-A)") (class "Default")
      (node (ref "LED4") (pin "2") (pinfunction "A_2") (pintype "passive"))
      (node (ref "R27") (pin "2") (pinfunction "2_2") (pintype "passive"))
    )
    (net (code "50") (name "Net-(LED5-A)") (class "Default")
      (node (ref "LED5") (pin "2") (pinfunction "A_2") (pintype "passive"))
      (node (ref "R28") (pin "2") (pinfunction "2_2") (pintype "passive"))
    )
    (net (code "51") (name "unconnected-(B2-NC-Pad4)") (class "Default")
      (node (ref "B2") (pin "4") (pinfunction "NC_4") (pintype "passive+no_connect"))
    )
    (net (code "52") (name "unconnected-(C5-Pad2)") (class "Default")
      (node (ref "C5") (pin "2") (pinfunction "2_2") (pintype "passive"))
    )
    (net (code "53") (name "unconnected-(IC1-AMP1_IN-Pad38)") (class "Default")
      (node (ref "IC1") (pin "38") (pinfunction "AMP1_IN_38") (pintype "passive+no_connect"))
    )
    (net (code "54") (name "unconnected-(IC1-AMP1_INB-Pad37)") (class "Default")
      (node (ref "IC1") (pin "37") (pinfunction "AMP1_INB_37") (pintype "passive+no_connect"))
    )
    (net (code "55") (name "unconnected-(IC1-B45_IN-Pad6)") (class "Default")
      (node (ref "IC1") (pin "6") (pinfunction "B45_IN_6") (pintype "passive"))
    )
    (net (code "56") (name "unconnected-(IC1-B45_INB-Pad7)") (class "Default")
      (node (ref "IC1") (pin "7") (pinfunction "B45_INB_7") (pintype "passive+no_connect"))
    )
    (net (code "57") (name "unconnected-(IC1-BND3_IN-Pad3)") (class "Default")
      (node (ref "IC1") (pin "3") (pinfunction "BND3_IN_3") (pintype "passive+no_connect"))
    )
    (net (code "58") (name "unconnected-(IC1-BND3_INB-Pad4)") (class "Default")
      (node (ref "IC1") (pin "4") (pinfunction "BND3_INB_4") (pintype "passive+no_connect"))
    )
    (net (code "59") (name "unconnected-(IC1-DC_FB-Pad17)") (class "Default")
      (node (ref "IC1") (pin "17") (pinfunction "DC_FB_17") (pintype "passive+no_connect"))
    )
    (net (code "60") (name "unconnected-(IC1-LBND_IN-Pad24)") (class "Default")
      (node (ref "IC1") (pin "24") (pinfunction "LBND_IN_24") (pintype "passive+no_connect"))
    )
    (net (code "61") (name "unconnected-(IC1-LBND_INB-Pad25)") (class "Default")
      (node (ref "IC1") (pin "25") (pinfunction "LBND_INB_25") (pintype "passive+no_connect"))
    )
    (net (code "62") (name "unconnected-(IC1-N{slash}C-Pad5)") (class "Default")
      (node (ref "IC1") (pin "5") (pinfunction "N/C_5") (pintype "passive+no_connect"))
    )
    (net (code "63") (name "unconnected-(IC1-OSC_OP-Pad16)") (class "Default")
      (node (ref "IC1") (pin "16") (pinfunction "OSC_OP_16") (pintype "passive+no_connect"))
    )
    (net (code "64") (name "unconnected-(IC1-U{slash}C-Pad13)") (class "Default")
      (node (ref "IC1") (pin "13") (pinfunction "U/C_13") (pintype "passive+no_connect"))
    )
    (net (code "65") (name "unconnected-(IC1-VHF_IN-Pad10)") (class "Default")
      (node (ref "IC1") (pin "10") (pinfunction "VHF_IN_10") (pintype "passive+no_connect"))
    )
    (net (code "66") (name "unconnected-(IC1-VHF_INB-Pad9)") (class "Default")
      (node (ref "IC1") (pin "9") (pinfunction "VHF_INB_9") (pintype "passive+no_connect"))
    )
    (net (code "67") (name "unconnected-(IC5-N{slash}C-Pad4)") (class "Default")
      (node (ref "IC5") (pin "4") (pinfunction "N/C_4") (pintype "passive+no_connect"))
    )
    (net (code "68") (name "unconnected-(J3-Pad4)") (class "Default")
      (node (ref "J3") (pin "4") (pinfunction "4_4") (pintype "passive+no_connect"))
    )
  )
)
